# Openlapse2_6.net
KiCad netlist of a schematic drawn in EAGLE
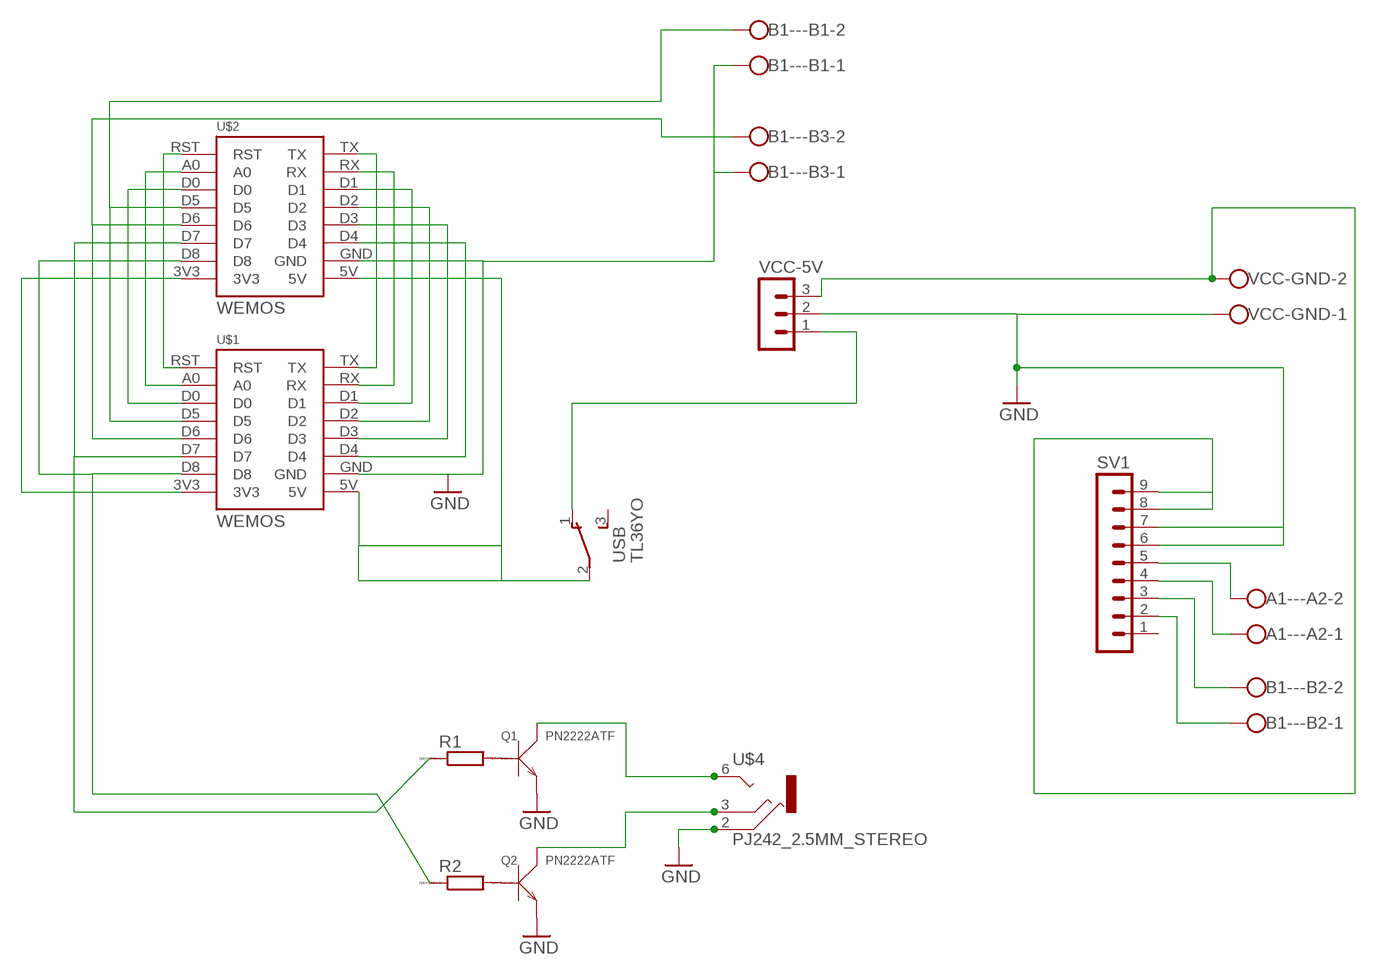
[diagram p0: schematic, sheet 1]

(export (version "E")
  (design (tool "Eeschema 10.0.6"))
  (components
    (comp (ref "A1---A2")
      (value "W237-102")
      (footprint "eagle-import:W237-102")
      (fields (field (name "MPN") "237-102"))
      (libsource (lib "eagle-import") (part "W237-102"))
    )
    (comp (ref "B1---B1")
      (value "W237-102")
      (footprint "eagle-import:W237-102")
      (fields (field (name "MPN") "237-102"))
      (libsource (lib "eagle-import") (part "W237-102"))
    )
    (comp (ref "B1---B2")
      (value "W237-102")
      (footprint "eagle-import:W237-102")
      (fields (field (name "MPN") "237-102"))
      (libsource (lib "eagle-import") (part "W237-102"))
    )
    (comp (ref "B1---B3")
      (value "W237-102")
      (footprint "eagle-import:W237-102")
      (fields (field (name "MPN") "237-102"))
      (libsource (lib "eagle-import") (part "W237-102"))
    )
    (comp (ref "Q1")
      (value "PN2222ATF")
      (footprint "eagle-import:TO-92")
      (libsource (lib "eagle-import") (part "DIP-TRANS-NPN-40V-1A-PN2222ATF(TO-92)"))
    )
    (comp (ref "Q2")
      (value "PN2222ATF")
      (footprint "eagle-import:TO-92")
      (libsource (lib "eagle-import") (part "DIP-TRANS-NPN-40V-1A-PN2222ATF(TO-92)"))
    )
    (comp (ref "R1")
      (value "R0204/7")
      (footprint "eagle-import:0204_7")
      (libsource (lib "eagle-import") (part "R0204/7"))
    )
    (comp (ref "R2")
      (value "R0204/7")
      (footprint "eagle-import:0204_7")
      (libsource (lib "eagle-import") (part "R0204/7"))
    )
    (comp (ref "SV1")
      (value "MA09-1")
      (footprint "eagle-import:MA09-1")
      (libsource (lib "eagle-import") (part "MA09-1"))
    )
    (comp (ref "U$1")
      (value "WEMOS")
      (footprint "eagle-import:WEMOS")
      (libsource (lib "eagle-import") (part "WEMOS"))
    )
    (comp (ref "U$2")
      (value "WEMOS")
      (footprint "eagle-import:WEMOS")
      (libsource (lib "eagle-import") (part "WEMOS"))
    )
    (comp (ref "U$4")
      (value "PJ242_2.5MM_STEREO")
      (footprint "eagle-import:PJ242_2.5MM_STEREO")
      (libsource (lib "eagle-import") (part "PJ242_2.5MM_STEREO"))
    )
    (comp (ref "USB")
      (value "TL36YO")
      (footprint "eagle-import:TL3XYO")
      (libsource (lib "eagle-import") (part "TL36YO"))
    )
    (comp (ref "VCC-5V")
      (value "MA03-1")
      (footprint "eagle-import:MA03-1")
      (libsource (lib "eagle-import") (part "MA03-1"))
    )
    (comp (ref "VCC-GND")
      (value "W237-102")
      (footprint "eagle-import:W237-102")
      (fields (field (name "MPN") "237-102"))
      (libsource (lib "eagle-import") (part "W237-102"))
    )
  )
  (nets
    (net (code "1") (name "GND") (class "Default")
      (node (ref "B1---B1") (pin "1") (pinfunction "KL_1") (pintype "passive"))
      (node (ref "B1---B3") (pin "1") (pinfunction "KL_1") (pintype "passive"))
      (node (ref "Q1") (pin "1") (pinfunction "E_1") (pintype "passive"))
      (node (ref "Q2") (pin "1") (pinfunction "E_1") (pintype "passive"))
      (node (ref "SV1") (pin "6") (pinfunction "6_6") (pintype "passive"))
      (node (ref "SV1") (pin "7") (pinfunction "7_7") (pintype "passive"))
      (node (ref "U$1") (pin "GND") (pinfunction "GND_GND") (pintype "bidirectional"))
      (node (ref "U$2") (pin "GND") (pinfunction "GND_GND") (pintype "bidirectional"))
      (node (ref "U$4") (pin "2") (pinfunction "1_2") (pintype "passive"))
      (node (ref "VCC-5V") (pin "2") (pinfunction "2_2") (pintype "passive"))
      (node (ref "VCC-GND") (pin "1") (pinfunction "KL_1") (pintype "passive"))
    )
    (net (code "2") (name "Net-(A1---A2A-KL)") (class "Default")
      (node (ref "A1---A2") (pin "1") (pinfunction "KL_1") (pintype "passive"))
      (node (ref "SV1") (pin "4") (pinfunction "4_4") (pintype "passive"))
    )
    (net (code "3") (name "Net-(A1---A2B-KL)") (class "Default")
      (node (ref "A1---A2") (pin "2") (pinfunction "KL_2") (pintype "passive"))
      (node (ref "SV1") (pin "5") (pinfunction "5_5") (pintype "passive"))
    )
    (net (code "4") (name "Net-(B1---B1B-KL)") (class "Default")
      (node (ref "B1---B1") (pin "2") (pinfunction "KL_2") (pintype "passive"))
      (node (ref "U$1") (pin "D5") (pinfunction "D5_D5") (pintype "bidirectional"))
      (node (ref "U$2") (pin "D5") (pinfunction "D5_D5") (pintype "bidirectional"))
    )
    (net (code "5") (name "Net-(B1---B2A-KL)") (class "Default")
      (node (ref "B1---B2") (pin "1") (pinfunction "KL_1") (pintype "passive"))
      (node (ref "SV1") (pin "2") (pinfunction "2_2") (pintype "passive"))
    )
    (net (code "6") (name "Net-(B1---B2B-KL)") (class "Default")
      (node (ref "B1---B2") (pin "2") (pinfunction "KL_2") (pintype "passive"))
      (node (ref "SV1") (pin "3") (pinfunction "3_3") (pintype "passive"))
    )
    (net (code "7") (name "Net-(B1---B3B-KL)") (class "Default")
      (node (ref "B1---B3") (pin "2") (pinfunction "KL_2") (pintype "passive"))
      (node (ref "U$1") (pin "D6") (pinfunction "D6_D6") (pintype "bidirectional"))
      (node (ref "U$2") (pin "D6") (pinfunction "D6_D6") (pintype "bidirectional"))
    )
    (net (code "8") (name "Net-(Q1-B)") (class "Default")
      (node (ref "Q1") (pin "2") (pinfunction "B_2") (pintype "passive"))
      (node (ref "R1") (pin "2") (pinfunction "2_2") (pintype "passive"))
    )
    (net (code "9") (name "Net-(Q1-C)") (class "Default")
      (node (ref "Q1") (pin "3") (pinfunction "C_3") (pintype "passive"))
      (node (ref "U$4") (pin "6") (pinfunction "2_6") (pintype "passive"))
    )
    (net (code "10") (name "Net-(Q2-B)") (class "Default")
      (node (ref "Q2") (pin "2") (pinfunction "B_2") (pintype "passive"))
      (node (ref "R2") (pin "2") (pinfunction "2_2") (pintype "passive"))
    )
    (net (code "11") (name "Net-(Q2-C)") (class "Default")
      (node (ref "Q2") (pin "3") (pinfunction "C_3") (pintype "passive"))
      (node (ref "U$4") (pin "3") (pinfunction "3_3") (pintype "passive"))
    )
    (net (code "12") (name "Net-(R1-Pad1)") (class "Default")
      (node (ref "R1") (pin "1") (pinfunction "1_1") (pintype "passive"))
      (node (ref "U$1") (pin "D7") (pinfunction "D7_D7") (pintype "bidirectional"))
      (node (ref "U$2") (pin "D7") (pinfunction "D7_D7") (pintype "bidirectional"))
    )
    (net (code "13") (name "Net-(R2-Pad1)") (class "Default")
      (node (ref "R2") (pin "1") (pinfunction "1_1") (pintype "passive"))
      (node (ref "U$1") (pin "D8") (pinfunction "D8_D8") (pintype "bidirectional"))
      (node (ref "U$2") (pin "D8") (pinfunction "D8_D8") (pintype "bidirectional"))
    )
    (net (code "14") (name "Net-(U$1-Pad3V3)") (class "Default")
      (node (ref "U$1") (pin "3V3") (pinfunction "3V3_3V3") (pintype "bidirectional"))
      (node (ref "U$2") (pin "3V3") (pinfunction "3V3_3V3") (pintype "bidirectional"))
    )
    (net (code "15") (name "Net-(U$1-PadA0)") (class "Default")
      (node (ref "U$1") (pin "A0") (pinfunction "A0_A0") (pintype "bidirectional"))
      (node (ref "U$2") (pin "A0") (pinfunction "A0_A0") (pintype "bidirectional"))
    )
    (net (code "16") (name "Net-(U$1-PadD0)") (class "Default")
      (node (ref "U$1") (pin "D0") (pinfunction "D0_D0") (pintype "bidirectional"))
      (node (ref "U$2") (pin "D0") (pinfunction "D0_D0") (pintype "bidirectional"))
    )
    (net (code "17") (name "Net-(U$1-PadD1)") (class "Default")
      (node (ref "U$1") (pin "D1") (pinfunction "D1_D1") (pintype "bidirectional"))
      (node (ref "U$2") (pin "D1") (pinfunction "D1_D1") (pintype "bidirectional"))
    )
    (net (code "18") (name "Net-(U$1-PadD2)") (class "Default")
      (node (ref "U$1") (pin "D2") (pinfunction "D2_D2") (pintype "bidirectional"))
      (node (ref "U$2") (pin "D2") (pinfunction "D2_D2") (pintype "bidirectional"))
    )
    (net (code "19") (name "Net-(U$1-PadD3)") (class "Default")
      (node (ref "U$1") (pin "D3") (pinfunction "D3_D3") (pintype "bidirectional"))
      (node (ref "U$2") (pin "D3") (pinfunction "D3_D3") (pintype "bidirectional"))
    )
    (net (code "20") (name "Net-(U$1-PadD4)") (class "Default")
      (node (ref "U$1") (pin "D4") (pinfunction "D4_D4") (pintype "bidirectional"))
      (node (ref "U$2") (pin "D4") (pinfunction "D4_D4") (pintype "bidirectional"))
    )
    (net (code "21") (name "Net-(U$1-PadRST)") (class "Default")
      (node (ref "U$1") (pin "RST") (pinfunction "RST_RST") (pintype "bidirectional"))
      (node (ref "U$2") (pin "RST") (pinfunction "RST_RST") (pintype "bidirectional"))
    )
    (net (code "22") (name "Net-(U$1-PadRX)") (class "Default")
      (node (ref "U$1") (pin "RX") (pinfunction "RX_RX") (pintype "bidirectional"))
      (node (ref "U$2") (pin "RX") (pinfunction "RX_RX") (pintype "bidirectional"))
    )
    (net (code "23") (name "Net-(U$1-PadTX)") (class "Default")
      (node (ref "U$1") (pin "TX") (pinfunction "TX_TX") (pintype "bidirectional"))
      (node (ref "U$2") (pin "TX") (pinfunction "TX_TX") (pintype "bidirectional"))
    )
    (net (code "24") (name "Net-(USB-O)") (class "Default")
      (node (ref "USB") (pin "1") (pinfunction "O_1") (pintype "passive"))
      (node (ref "VCC-5V") (pin "1") (pinfunction "1_1") (pintype "passive"))
    )
    (net (code "25") (name "Net-(USB-P)") (class "Default")
      (node (ref "U$1") (pin "5V") (pinfunction "5V_5V") (pintype "bidirectional"))
      (node (ref "U$2") (pin "5V") (pinfunction "5V_5V") (pintype "bidirectional"))
      (node (ref "USB") (pin "2") (pinfunction "P_2") (pintype "passive"))
    )
    (net (code "26") (name "Net-(VCC-GNDB-KL)") (class "Default")
      (node (ref "SV1") (pin "8") (pinfunction "8_8") (pintype "passive"))
      (node (ref "SV1") (pin "9") (pinfunction "9_9") (pintype "passive"))
      (node (ref "VCC-5V") (pin "3") (pinfunction "3_3") (pintype "passive"))
      (node (ref "VCC-GND") (pin "2") (pinfunction "KL_2") (pintype "passive"))
    )
    (net (code "27") (name "unconnected-(SV1-Pad1)") (class "Default")
      (node (ref "SV1") (pin "1") (pinfunction "1_1") (pintype "passive"))
    )
    (net (code "28") (name "unconnected-(USB-S-Pad3)") (class "Default")
      (node (ref "USB") (pin "3") (pinfunction "S_3") (pintype "passive"))
    )
  )
)
